# SmartCup.net
KiCad netlist of a schematic drawn in EAGLE
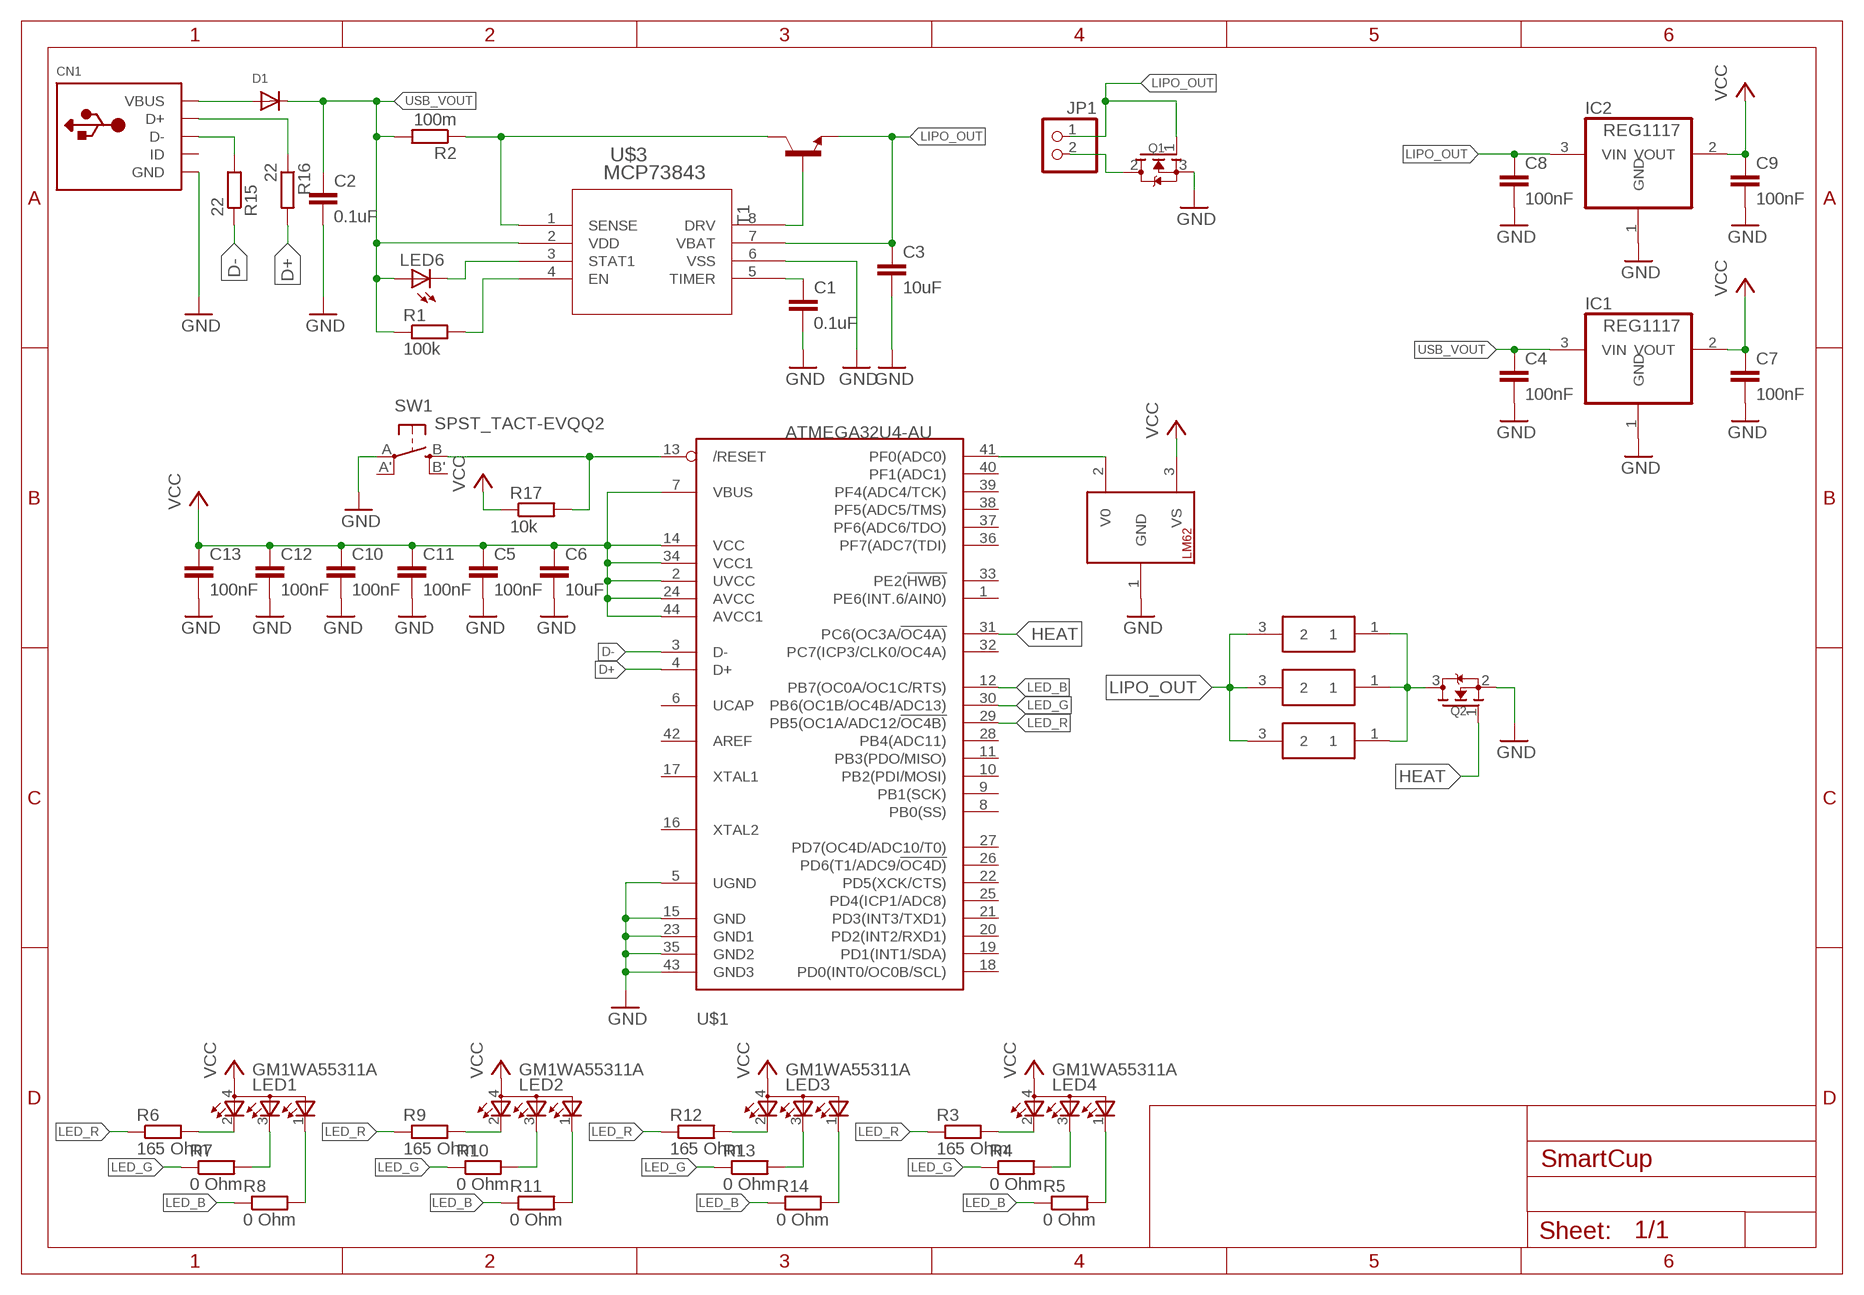
[diagram p0: schematic, sheet 1]

(export (version "E")
  (design (tool "Eeschema 10.0.6"))
  (components
    (comp (ref "C1")
      (value "0.1uF")
      (footprint "eagle-import:C0603")
      (libsource (lib "eagle-import") (part "C-EUC0603"))
    )
    (comp (ref "C2")
      (value "0.1uF")
      (footprint "eagle-import:C0603")
      (libsource (lib "eagle-import") (part "C-EUC0603"))
    )
    (comp (ref "C3")
      (value "10uF")
      (footprint "eagle-import:C0603")
      (libsource (lib "eagle-import") (part "C-EUC0603"))
    )
    (comp (ref "C4")
      (value "100nF")
      (footprint "eagle-import:C0603")
      (libsource (lib "eagle-import") (part "C-EUC0603"))
    )
    (comp (ref "C5")
      (value "100nF")
      (footprint "eagle-import:C0603")
      (libsource (lib "eagle-import") (part "C-EUC0603"))
    )
    (comp (ref "C6")
      (value "10uF")
      (footprint "eagle-import:C0805")
      (libsource (lib "eagle-import") (part "C-EUC0805"))
    )
    (comp (ref "C7")
      (value "100nF")
      (footprint "eagle-import:C0603")
      (libsource (lib "eagle-import") (part "C-EUC0603"))
    )
    (comp (ref "C8")
      (value "100nF")
      (footprint "eagle-import:C0603")
      (libsource (lib "eagle-import") (part "C-EUC0603"))
    )
    (comp (ref "C9")
      (value "100nF")
      (footprint "eagle-import:C0603")
      (libsource (lib "eagle-import") (part "C-EUC0603"))
    )
    (comp (ref "C10")
      (value "100nF")
      (footprint "eagle-import:C0603")
      (libsource (lib "eagle-import") (part "C-EUC0603"))
    )
    (comp (ref "C11")
      (value "100nF")
      (footprint "eagle-import:C0603")
      (libsource (lib "eagle-import") (part "C-EUC0603"))
    )
    (comp (ref "C12")
      (value "100nF")
      (footprint "eagle-import:C0603")
      (libsource (lib "eagle-import") (part "C-EUC0603"))
    )
    (comp (ref "C13")
      (value "100nF")
      (footprint "eagle-import:C0603")
      (libsource (lib "eagle-import") (part "C-EUC0603"))
    )
    (comp (ref "CN1")
      (value "USBMINIB")
      (footprint "eagle-import:USB-MINIB")
      (libsource (lib "eagle-import") (part "USBMINIB"))
    )
    (comp (ref "D1")
      (value "DIODE_SOD-123FL")
      (footprint "eagle-import:SOD-123FL")
      (libsource (lib "eagle-import") (part "DIODE_SOD-123FL"))
    )
    (comp (ref "IC1")
      (value "REG1117")
      (footprint "eagle-import:SOT223")
      (libsource (lib "eagle-import") (part "REG1117"))
    )
    (comp (ref "IC2")
      (value "REG1117")
      (footprint "eagle-import:SOT223")
      (libsource (lib "eagle-import") (part "REG1117"))
    )
    (comp (ref "JP1")
      (value "PINHD-1X2")
      (footprint "eagle-import:1X02")
      (libsource (lib "eagle-import") (part "PINHD-1X2"))
    )
    (comp (ref "LED1")
      (value "GM1WA55311A")
      (footprint "eagle-import:GM1WA55311A")
      (libsource (lib "eagle-import") (part "GM1WA55311A"))
    )
    (comp (ref "LED2")
      (value "GM1WA55311A")
      (footprint "eagle-import:GM1WA55311A")
      (libsource (lib "eagle-import") (part "GM1WA55311A"))
    )
    (comp (ref "LED3")
      (value "GM1WA55311A")
      (footprint "eagle-import:GM1WA55311A")
      (libsource (lib "eagle-import") (part "GM1WA55311A"))
    )
    (comp (ref "LED4")
      (value "GM1WA55311A")
      (footprint "eagle-import:GM1WA55311A")
      (libsource (lib "eagle-import") (part "GM1WA55311A"))
    )
    (comp (ref "LED6")
      (value "LEDCHIP-LED0603")
      (footprint "eagle-import:CHIP-LED0603")
      (libsource (lib "eagle-import") (part "LEDCHIP-LED0603"))
    )
    (comp (ref "Q1")
      (value "MOSFET-NSOT223")
      (footprint "eagle-import:SOT223")
      (libsource (lib "eagle-import") (part "MOSFET-NSOT223"))
    )
    (comp (ref "Q2")
      (value "MOSFET-NREFLOW")
      (footprint "eagle-import:SOT23")
      (libsource (lib "eagle-import") (part "MOSFET-NREFLOW"))
    )
    (comp (ref "R1")
      (value "100k")
      (footprint "eagle-import:R0603")
      (libsource (lib "eagle-import") (part "R-EU_R0603"))
    )
    (comp (ref "R2")
      (value "100m")
      (footprint "eagle-import:R0603")
      (libsource (lib "eagle-import") (part "R-EU_R0603"))
    )
    (comp (ref "R3")
      (value "165 Ohm")
      (footprint "eagle-import:R0603")
      (libsource (lib "eagle-import") (part "R-EU_R0603"))
    )
    (comp (ref "R4")
      (value "0 Ohm")
      (footprint "eagle-import:R0603")
      (libsource (lib "eagle-import") (part "R-EU_R0603"))
    )
    (comp (ref "R5")
      (value "0 Ohm")
      (footprint "eagle-import:R0603")
      (libsource (lib "eagle-import") (part "R-EU_R0603"))
    )
    (comp (ref "R6")
      (value "165 Ohm")
      (footprint "eagle-import:R0603")
      (libsource (lib "eagle-import") (part "R-EU_R0603"))
    )
    (comp (ref "R7")
      (value "0 Ohm")
      (footprint "eagle-import:R0603")
      (libsource (lib "eagle-import") (part "R-EU_R0603"))
    )
    (comp (ref "R8")
      (value "0 Ohm")
      (footprint "eagle-import:R0603")
      (libsource (lib "eagle-import") (part "R-EU_R0603"))
    )
    (comp (ref "R9")
      (value "165 Ohm")
      (footprint "eagle-import:R0603")
      (libsource (lib "eagle-import") (part "R-EU_R0603"))
    )
    (comp (ref "R10")
      (value "0 Ohm")
      (footprint "eagle-import:R0603")
      (libsource (lib "eagle-import") (part "R-EU_R0603"))
    )
    (comp (ref "R11")
      (value "0 Ohm")
      (footprint "eagle-import:R0603")
      (libsource (lib "eagle-import") (part "R-EU_R0603"))
    )
    (comp (ref "R12")
      (value "165 Ohm")
      (footprint "eagle-import:R0603")
      (libsource (lib "eagle-import") (part "R-EU_R0603"))
    )
    (comp (ref "R13")
      (value "0 Ohm")
      (footprint "eagle-import:R0603")
      (libsource (lib "eagle-import") (part "R-EU_R0603"))
    )
    (comp (ref "R14")
      (value "0 Ohm")
      (footprint "eagle-import:R0603")
      (libsource (lib "eagle-import") (part "R-EU_R0603"))
    )
    (comp (ref "R15")
      (value "22")
      (footprint "eagle-import:R0603")
      (libsource (lib "eagle-import") (part "R-EU_R0603"))
    )
    (comp (ref "R16")
      (value "22")
      (footprint "eagle-import:R0603")
      (libsource (lib "eagle-import") (part "R-EU_R0603"))
    )
    (comp (ref "R17")
      (value "10k")
      (footprint "eagle-import:R0603")
      (libsource (lib "eagle-import") (part "R-EU_R0603"))
    )
    (comp (ref "SW1")
      (value "SPST_TACT-EVQQ2")
      (footprint "eagle-import:EVQ-Q2")
      (libsource (lib "eagle-import") (part "SPST_TACT-EVQQ2"))
    )
    (comp (ref "T1")
      (value "-NPN-SOT23-EBC")
      (footprint "eagle-import:SOT23-EBC")
      (libsource (lib "eagle-import") (part "-NPN-SOT23-EBC"))
    )
    (comp (ref "U$1")
      (value "ATMEGA32U4-AU")
      (footprint "eagle-import:TQFP44")
      (libsource (lib "eagle-import") (part "ATMEGA32U4-AU"))
    )
    (comp (ref "U$3")
      (value "MCP73843")
      (footprint "eagle-import:MSOP8_MC")
      (libsource (lib "eagle-import") (part "MCP73843"))
    )
    (comp (ref "U$4")
      (value "LM62TO-92")
      (footprint "eagle-import:TO92-")
      (libsource (lib "eagle-import") (part "LM62TO-92"))
    )
    (comp (ref "U$6")
      (value "BOURNS_PWR")
      (footprint "eagle-import:DPAK")
      (libsource (lib "eagle-import") (part "BOURNS_PWR"))
    )
    (comp (ref "U$7")
      (value "BOURNS_PWR")
      (footprint "eagle-import:DPAK")
      (libsource (lib "eagle-import") (part "BOURNS_PWR"))
    )
    (comp (ref "U$8")
      (value "BOURNS_PWR")
      (footprint "eagle-import:DPAK")
      (libsource (lib "eagle-import") (part "BOURNS_PWR"))
    )
  )
  (nets
    (net (code "1") (name "D+") (class "Default")
      (node (ref "R16") (pin "2") (pinfunction "2_2") (pintype "passive"))
      (node (ref "U$1") (pin "4") (pinfunction "D+_4") (pintype "bidirectional"))
    )
    (net (code "2") (name "D-") (class "Default")
      (node (ref "R15") (pin "1") (pinfunction "1_1") (pintype "passive"))
      (node (ref "U$1") (pin "3") (pinfunction "D-_3") (pintype "bidirectional"))
    )
    (net (code "3") (name "GND") (class "Default")
      (node (ref "C1") (pin "2") (pinfunction "2_2") (pintype "passive"))
      (node (ref "C10") (pin "2") (pinfunction "2_2") (pintype "passive"))
      (node (ref "C11") (pin "2") (pinfunction "2_2") (pintype "passive"))
      (node (ref "C12") (pin "2") (pinfunction "2_2") (pintype "passive"))
      (node (ref "C13") (pin "2") (pinfunction "2_2") (pintype "passive"))
      (node (ref "C2") (pin "2") (pinfunction "2_2") (pintype "passive"))
      (node (ref "C3") (pin "2") (pinfunction "2_2") (pintype "passive"))
      (node (ref "C4") (pin "2") (pinfunction "2_2") (pintype "passive"))
      (node (ref "C5") (pin "2") (pinfunction "2_2") (pintype "passive"))
      (node (ref "C6") (pin "2") (pinfunction "2_2") (pintype "passive"))
      (node (ref "C7") (pin "2") (pinfunction "2_2") (pintype "passive"))
      (node (ref "C8") (pin "2") (pinfunction "2_2") (pintype "passive"))
      (node (ref "C9") (pin "2") (pinfunction "2_2") (pintype "passive"))
      (node (ref "CN1") (pin "GND") (pinfunction "GND_GND") (pintype "power_in"))
      (node (ref "IC1") (pin "1") (pinfunction "GND_1") (pintype "power_in"))
      (node (ref "IC2") (pin "1") (pinfunction "GND_1") (pintype "power_in"))
      (node (ref "Q1") (pin "3") (pinfunction "S_3") (pintype "bidirectional"))
      (node (ref "Q2") (pin "2") (pinfunction "S_2") (pintype "bidirectional"))
      (node (ref "SW1") (pin "A") (pinfunction "P_A") (pintype "passive"))
      (node (ref "U$1") (pin "15") (pinfunction "GND_15") (pintype "bidirectional"))
      (node (ref "U$1") (pin "23") (pinfunction "GND1_23") (pintype "bidirectional"))
      (node (ref "U$1") (pin "35") (pinfunction "GND2_35") (pintype "bidirectional"))
      (node (ref "U$1") (pin "43") (pinfunction "GND3_43") (pintype "bidirectional"))
      (node (ref "U$1") (pin "5") (pinfunction "UGND_5") (pintype "bidirectional"))
      (node (ref "U$3") (pin "6") (pinfunction "VSS_6") (pintype "passive"))
      (node (ref "U$4") (pin "1") (pinfunction "GND_1") (pintype "bidirectional"))
    )
    (net (code "4") (name "HEAT") (class "Default")
      (node (ref "Q2") (pin "1") (pinfunction "G_1") (pintype "bidirectional"))
      (node (ref "U$1") (pin "31") (pinfunction "PC6(OC3A/~{OC4A})_31") (pintype "bidirectional"))
    )
    (net (code "5") (name "LED_B") (class "Default")
      (node (ref "R11") (pin "1") (pinfunction "1_1") (pintype "passive"))
      (node (ref "R14") (pin "1") (pinfunction "1_1") (pintype "passive"))
      (node (ref "R5") (pin "1") (pinfunction "1_1") (pintype "passive"))
      (node (ref "R8") (pin "1") (pinfunction "1_1") (pintype "passive"))
      (node (ref "U$1") (pin "12") (pinfunction "PB7(OC0A/OC1C/RTS)_12") (pintype "bidirectional"))
    )
    (net (code "6") (name "LED_G") (class "Default")
      (node (ref "R10") (pin "1") (pinfunction "1_1") (pintype "passive"))
      (node (ref "R13") (pin "1") (pinfunction "1_1") (pintype "passive"))
      (node (ref "R4") (pin "1") (pinfunction "1_1") (pintype "passive"))
      (node (ref "R7") (pin "1") (pinfunction "1_1") (pintype "passive"))
      (node (ref "U$1") (pin "30") (pinfunction "PB6(OC1B/OC4B/ADC13)_30") (pintype "bidirectional"))
    )
    (net (code "7") (name "LED_R") (class "Default")
      (node (ref "R12") (pin "1") (pinfunction "1_1") (pintype "passive"))
      (node (ref "R3") (pin "1") (pinfunction "1_1") (pintype "passive"))
      (node (ref "R6") (pin "1") (pinfunction "1_1") (pintype "passive"))
      (node (ref "R9") (pin "1") (pinfunction "1_1") (pintype "passive"))
      (node (ref "U$1") (pin "29") (pinfunction "PB5(OC1A/ADC12/~{OC4B})_29") (pintype "bidirectional"))
    )
    (net (code "8") (name "LIPO_OUT") (class "Default")
      (node (ref "C3") (pin "1") (pinfunction "1_1") (pintype "passive"))
      (node (ref "C8") (pin "1") (pinfunction "1_1") (pintype "passive"))
      (node (ref "IC2") (pin "3") (pinfunction "VIN_3") (pintype "input"))
      (node (ref "JP1") (pin "1") (pinfunction "1_1") (pintype "passive"))
      (node (ref "Q1") (pin "1") (pinfunction "G_1") (pintype "bidirectional"))
      (node (ref "T1") (pin "E") (pinfunction "E_E") (pintype "passive"))
      (node (ref "U$3") (pin "7") (pinfunction "VBAT_7") (pintype "passive"))
      (node (ref "U$6") (pin "3") (pinfunction "2_3") (pintype "bidirectional"))
      (node (ref "U$7") (pin "3") (pinfunction "2_3") (pintype "bidirectional"))
      (node (ref "U$8") (pin "3") (pinfunction "2_3") (pintype "bidirectional"))
    )
    (net (code "9") (name "Net-(CN1-PadD+)") (class "Default")
      (node (ref "CN1") (pin "D+") (pinfunction "D+_D+") (pintype "bidirectional"))
      (node (ref "R16") (pin "1") (pinfunction "1_1") (pintype "passive"))
    )
    (net (code "10") (name "Net-(CN1-PadD-)") (class "Default")
      (node (ref "CN1") (pin "D-") (pinfunction "D-_D-") (pintype "bidirectional"))
      (node (ref "R15") (pin "2") (pinfunction "2_2") (pintype "passive"))
    )
    (net (code "11") (name "Net-(CN1-PadVBUS)") (class "Default")
      (node (ref "CN1") (pin "VBUS") (pinfunction "VBUS_VBUS") (pintype "power_in"))
      (node (ref "D1") (pin "A") (pinfunction "A_A") (pintype "passive"))
    )
    (net (code "12") (name "Net-(LED1-CBLUE)") (class "Default")
      (node (ref "LED1") (pin "3") (pinfunction "CBLUE_3") (pintype "passive"))
      (node (ref "R7") (pin "2") (pinfunction "2_2") (pintype "passive"))
    )
    (net (code "13") (name "Net-(LED1-CGREEN)") (class "Default")
      (node (ref "LED1") (pin "1") (pinfunction "CGREEN_1") (pintype "passive"))
      (node (ref "R8") (pin "2") (pinfunction "2_2") (pintype "passive"))
    )
    (net (code "14") (name "Net-(LED1-CRED)") (class "Default")
      (node (ref "LED1") (pin "2") (pinfunction "CRED_2") (pintype "passive"))
      (node (ref "R6") (pin "2") (pinfunction "2_2") (pintype "passive"))
    )
    (net (code "15") (name "Net-(LED2-CBLUE)") (class "Default")
      (node (ref "LED2") (pin "3") (pinfunction "CBLUE_3") (pintype "passive"))
      (node (ref "R10") (pin "2") (pinfunction "2_2") (pintype "passive"))
    )
    (net (code "16") (name "Net-(LED2-CGREEN)") (class "Default")
      (node (ref "LED2") (pin "1") (pinfunction "CGREEN_1") (pintype "passive"))
      (node (ref "R11") (pin "2") (pinfunction "2_2") (pintype "passive"))
    )
    (net (code "17") (name "Net-(LED2-CRED)") (class "Default")
      (node (ref "LED2") (pin "2") (pinfunction "CRED_2") (pintype "passive"))
      (node (ref "R9") (pin "2") (pinfunction "2_2") (pintype "passive"))
    )
    (net (code "18") (name "Net-(LED3-CBLUE)") (class "Default")
      (node (ref "LED3") (pin "3") (pinfunction "CBLUE_3") (pintype "passive"))
      (node (ref "R13") (pin "2") (pinfunction "2_2") (pintype "passive"))
    )
    (net (code "19") (name "Net-(LED3-CGREEN)") (class "Default")
      (node (ref "LED3") (pin "1") (pinfunction "CGREEN_1") (pintype "passive"))
      (node (ref "R14") (pin "2") (pinfunction "2_2") (pintype "passive"))
    )
    (net (code "20") (name "Net-(LED3-CRED)") (class "Default")
      (node (ref "LED3") (pin "2") (pinfunction "CRED_2") (pintype "passive"))
      (node (ref "R12") (pin "2") (pinfunction "2_2") (pintype "passive"))
    )
    (net (code "21") (name "Net-(LED4-CBLUE)") (class "Default")
      (node (ref "LED4") (pin "3") (pinfunction "CBLUE_3") (pintype "passive"))
      (node (ref "R4") (pin "2") (pinfunction "2_2") (pintype "passive"))
    )
    (net (code "22") (name "Net-(LED4-CGREEN)") (class "Default")
      (node (ref "LED4") (pin "1") (pinfunction "CGREEN_1") (pintype "passive"))
      (node (ref "R5") (pin "2") (pinfunction "2_2") (pintype "passive"))
    )
    (net (code "23") (name "Net-(LED4-CRED)") (class "Default")
      (node (ref "LED4") (pin "2") (pinfunction "CRED_2") (pintype "passive"))
      (node (ref "R3") (pin "2") (pinfunction "2_2") (pintype "passive"))
    )
    (net (code "24") (name "Net-(Q1-D)") (class "Default")
      (node (ref "JP1") (pin "2") (pinfunction "2_2") (pintype "passive"))
      (node (ref "Q1") (pin "2") (pinfunction "D_2") (pintype "bidirectional"))
    )
    (net (code "25") (name "Net-(Q2-D)") (class "Default")
      (node (ref "Q2") (pin "3") (pinfunction "D_3") (pintype "bidirectional"))
      (node (ref "U$6") (pin "1") (pinfunction "1_1") (pintype "bidirectional"))
      (node (ref "U$7") (pin "1") (pinfunction "1_1") (pintype "bidirectional"))
      (node (ref "U$8") (pin "1") (pinfunction "1_1") (pintype "bidirectional"))
    )
    (net (code "26") (name "Net-(SW1-S)") (class "Default")
      (node (ref "R17") (pin "2") (pinfunction "2_2") (pintype "passive"))
      (node (ref "SW1") (pin "B") (pinfunction "S_B") (pintype "passive"))
      (node (ref "U$1") (pin "13") (pinfunction "/RESET_13") (pintype "bidirectional"))
    )
    (net (code "27") (name "Net-(U$1-PF0(ADC0))") (class "Default")
      (node (ref "U$1") (pin "41") (pinfunction "PF0(ADC0)_41") (pintype "bidirectional"))
      (node (ref "U$4") (pin "2") (pinfunction "V0_2") (pintype "bidirectional"))
    )
    (net (code "28") (name "Net-(U$3-DRV)") (class "Default")
      (node (ref "T1") (pin "B") (pinfunction "B_B") (pintype "passive"))
      (node (ref "U$3") (pin "8") (pinfunction "DRV_8") (pintype "passive"))
    )
    (net (code "29") (name "Net-(U$3-EN)") (class "Default")
      (node (ref "R1") (pin "2") (pinfunction "2_2") (pintype "passive"))
      (node (ref "U$3") (pin "4") (pinfunction "EN_4") (pintype "passive"))
    )
    (net (code "30") (name "Net-(U$3-SENSE)") (class "Default")
      (node (ref "R2") (pin "1") (pinfunction "1_1") (pintype "passive"))
      (node (ref "T1") (pin "C") (pinfunction "C_C") (pintype "passive"))
      (node (ref "U$3") (pin "1") (pinfunction "SENSE_1") (pintype "passive"))
    )
    (net (code "31") (name "Net-(U$3-STAT1)") (class "Default")
      (node (ref "LED6") (pin "C") (pinfunction "C_C") (pintype "passive"))
      (node (ref "U$3") (pin "3") (pinfunction "STAT1_3") (pintype "passive"))
    )
    (net (code "32") (name "Net-(U$3-TIMER)") (class "Default")
      (node (ref "C1") (pin "1") (pinfunction "1_1") (pintype "passive"))
      (node (ref "U$3") (pin "5") (pinfunction "TIMER_5") (pintype "passive"))
    )
    (net (code "33") (name "USB_VOUT") (class "Default")
      (node (ref "C2") (pin "1") (pinfunction "1_1") (pintype "passive"))
      (node (ref "C4") (pin "1") (pinfunction "1_1") (pintype "passive"))
      (node (ref "D1") (pin "C") (pinfunction "C_C") (pintype "passive"))
      (node (ref "IC1") (pin "3") (pinfunction "VIN_3") (pintype "input"))
      (node (ref "LED6") (pin "A") (pinfunction "A_A") (pintype "passive"))
      (node (ref "R1") (pin "1") (pinfunction "1_1") (pintype "passive"))
      (node (ref "R2") (pin "2") (pinfunction "2_2") (pintype "passive"))
      (node (ref "U$3") (pin "2") (pinfunction "VDD_2") (pintype "passive"))
    )
    (net (code "34") (name "VCC") (class "Default")
      (node (ref "C10") (pin "1") (pinfunction "1_1") (pintype "passive"))
      (node (ref "C11") (pin "1") (pinfunction "1_1") (pintype "passive"))
      (node (ref "C12") (pin "1") (pinfunction "1_1") (pintype "passive"))
      (node (ref "C13") (pin "1") (pinfunction "1_1") (pintype "passive"))
      (node (ref "C5") (pin "1") (pinfunction "1_1") (pintype "passive"))
      (node (ref "C6") (pin "1") (pinfunction "1_1") (pintype "passive"))
      (node (ref "C7") (pin "1") (pinfunction "1_1") (pintype "passive"))
      (node (ref "C9") (pin "1") (pinfunction "1_1") (pintype "passive"))
      (node (ref "IC1") (pin "2") (pinfunction "VOUT_2") (pintype "output"))
      (node (ref "IC2") (pin "2") (pinfunction "VOUT_2") (pintype "output"))
      (node (ref "LED1") (pin "4") (pinfunction "A_4") (pintype "passive"))
      (node (ref "LED2") (pin "4") (pinfunction "A_4") (pintype "passive"))
      (node (ref "LED3") (pin "4") (pinfunction "A_4") (pintype "passive"))
      (node (ref "LED4") (pin "4") (pinfunction "A_4") (pintype "passive"))
      (node (ref "R17") (pin "1") (pinfunction "1_1") (pintype "passive"))
      (node (ref "U$1") (pin "14") (pinfunction "VCC_14") (pintype "bidirectional"))
      (node (ref "U$1") (pin "2") (pinfunction "UVCC_2") (pintype "bidirectional"))
      (node (ref "U$1") (pin "24") (pinfunction "AVCC_24") (pintype "bidirectional"))
      (node (ref "U$1") (pin "34") (pinfunction "VCC1_34") (pintype "bidirectional"))
      (node (ref "U$1") (pin "44") (pinfunction "AVCC1_44") (pintype "bidirectional"))
      (node (ref "U$1") (pin "7") (pinfunction "VBUS_7") (pintype "bidirectional"))
      (node (ref "U$4") (pin "3") (pinfunction "VS_3") (pintype "bidirectional"))
    )
    (net (code "35") (name "unconnected-(CN1-PadID)") (class "Default")
      (node (ref "CN1") (pin "ID") (pinfunction "ID_ID") (pintype "bidirectional"))
    )
    (net (code "36") (name "unconnected-(SW1-P1-PadA')") (class "Default")
      (node (ref "SW1") (pin "A'") (pinfunction "P1_A'") (pintype "passive"))
    )
    (net (code "37") (name "unconnected-(SW1-S1-PadB')") (class "Default")
      (node (ref "SW1") (pin "B'") (pinfunction "S1_B'") (pintype "passive"))
    )
    (net (code "38") (name "unconnected-(U$1-AREF-Pad42)") (class "Default")
      (node (ref "U$1") (pin "42") (pinfunction "AREF_42") (pintype "bidirectional"))
    )
    (net (code "39") (name "unconnected-(U$1-PB0(SS)-Pad8)") (class "Default")
      (node (ref "U$1") (pin "8") (pinfunction "PB0(SS)_8") (pintype "bidirectional"))
    )
    (net (code "40") (name "unconnected-(U$1-PB1(SCK)-Pad9)") (class "Default")
      (node (ref "U$1") (pin "9") (pinfunction "PB1(SCK)_9") (pintype "bidirectional"))
    )
    (net (code "41") (name "unconnected-(U$1-PB2(PDI{slash}MOSI)-Pad10)") (class "Default")
      (node (ref "U$1") (pin "10") (pinfunction "PB2(PDI/MOSI)_10") (pintype "bidirectional"))
    )
    (net (code "42") (name "unconnected-(U$1-PB3(PDO{slash}MISO)-Pad11)") (class "Default")
      (node (ref "U$1") (pin "11") (pinfunction "PB3(PDO/MISO)_11") (pintype "bidirectional"))
    )
    (net (code "43") (name "unconnected-(U$1-PB4(ADC11)-Pad28)") (class "Default")
      (node (ref "U$1") (pin "28") (pinfunction "PB4(ADC11)_28") (pintype "bidirectional"))
    )
    (net (code "44") (name "unconnected-(U$1-PC7(ICP3{slash}CLK0{slash}OC4A)-Pad32)") (class "Default")
      (node (ref "U$1") (pin "32") (pinfunction "PC7(ICP3/CLK0/OC4A)_32") (pintype "bidirectional"))
    )
    (net (code "45") (name "unconnected-(U$1-PD0(INT0{slash}OC0B{slash}SCL)-Pad18)") (class "Default")
      (node (ref "U$1") (pin "18") (pinfunction "PD0(INT0/OC0B/SCL)_18") (pintype "bidirectional"))
    )
    (net (code "46") (name "unconnected-(U$1-PD1(INT1{slash}SDA)-Pad19)") (class "Default")
      (node (ref "U$1") (pin "19") (pinfunction "PD1(INT1/SDA)_19") (pintype "bidirectional"))
    )
    (net (code "47") (name "unconnected-(U$1-PD2(INT2{slash}RXD1)-Pad20)") (class "Default")
      (node (ref "U$1") (pin "20") (pinfunction "PD2(INT2/RXD1)_20") (pintype "bidirectional"))
    )
    (net (code "48") (name "unconnected-(U$1-PD3(INT3{slash}TXD1)-Pad21)") (class "Default")
      (node (ref "U$1") (pin "21") (pinfunction "PD3(INT3/TXD1)_21") (pintype "bidirectional"))
    )
    (net (code "49") (name "unconnected-(U$1-PD4(ICP1{slash}ADC8)-Pad25)") (class "Default")
      (node (ref "U$1") (pin "25") (pinfunction "PD4(ICP1/ADC8)_25") (pintype "bidirectional"))
    )
    (net (code "50") (name "unconnected-(U$1-PD5(XCK{slash}CTS)-Pad22)") (class "Default")
      (node (ref "U$1") (pin "22") (pinfunction "PD5(XCK/CTS)_22") (pintype "bidirectional"))
    )
    (net (code "51") (name "unconnected-(U$1-PD6(T1{slash}ADC9{slash}~{OC4D})-Pad26)") (class "Default")
      (node (ref "U$1") (pin "26") (pinfunction "PD6(T1/ADC9/~{OC4D})_26") (pintype "bidirectional"))
    )
    (net (code "52") (name "unconnected-(U$1-PD7(OC4D{slash}ADC10{slash}T0)-Pad27)") (class "Default")
      (node (ref "U$1") (pin "27") (pinfunction "PD7(OC4D/ADC10/T0)_27") (pintype "bidirectional"))
    )
    (net (code "53") (name "unconnected-(U$1-PE2(~{HWB})-Pad33)") (class "Default")
      (node (ref "U$1") (pin "33") (pinfunction "PE2(~{HWB})_33") (pintype "bidirectional"))
    )
    (net (code "54") (name "unconnected-(U$1-PE6(INT.6{slash}AIN0)-Pad1)") (class "Default")
      (node (ref "U$1") (pin "1") (pinfunction "PE6(INT.6/AIN0)_1") (pintype "bidirectional"))
    )
    (net (code "55") (name "unconnected-(U$1-PF1(ADC1)-Pad40)") (class "Default")
      (node (ref "U$1") (pin "40") (pinfunction "PF1(ADC1)_40") (pintype "bidirectional"))
    )
    (net (code "56") (name "unconnected-(U$1-PF4(ADC4{slash}TCK)-Pad39)") (class "Default")
      (node (ref "U$1") (pin "39") (pinfunction "PF4(ADC4/TCK)_39") (pintype "bidirectional"))
    )
    (net (code "57") (name "unconnected-(U$1-PF5(ADC5{slash}TMS)-Pad38)") (class "Default")
      (node (ref "U$1") (pin "38") (pinfunction "PF5(ADC5/TMS)_38") (pintype "bidirectional"))
    )
    (net (code "58") (name "unconnected-(U$1-PF6(ADC6{slash}TDO)-Pad37)") (class "Default")
      (node (ref "U$1") (pin "37") (pinfunction "PF6(ADC6/TDO)_37") (pintype "bidirectional"))
    )
    (net (code "59") (name "unconnected-(U$1-PF7(ADC7(TDI)-Pad36)") (class "Default")
      (node (ref "U$1") (pin "36") (pinfunction "PF7(ADC7(TDI)_36") (pintype "bidirectional"))
    )
    (net (code "60") (name "unconnected-(U$1-UCAP-Pad6)") (class "Default")
      (node (ref "U$1") (pin "6") (pinfunction "UCAP_6") (pintype "bidirectional"))
    )
    (net (code "61") (name "unconnected-(U$1-XTAL1-Pad17)") (class "Default")
      (node (ref "U$1") (pin "17") (pinfunction "XTAL1_17") (pintype "bidirectional"))
    )
    (net (code "62") (name "unconnected-(U$1-XTAL2-Pad16)") (class "Default")
      (node (ref "U$1") (pin "16") (pinfunction "XTAL2_16") (pintype "bidirectional"))
    )
  )
)
